# Main.net
KiCad netlist of a schematic drawn in Altium Designer
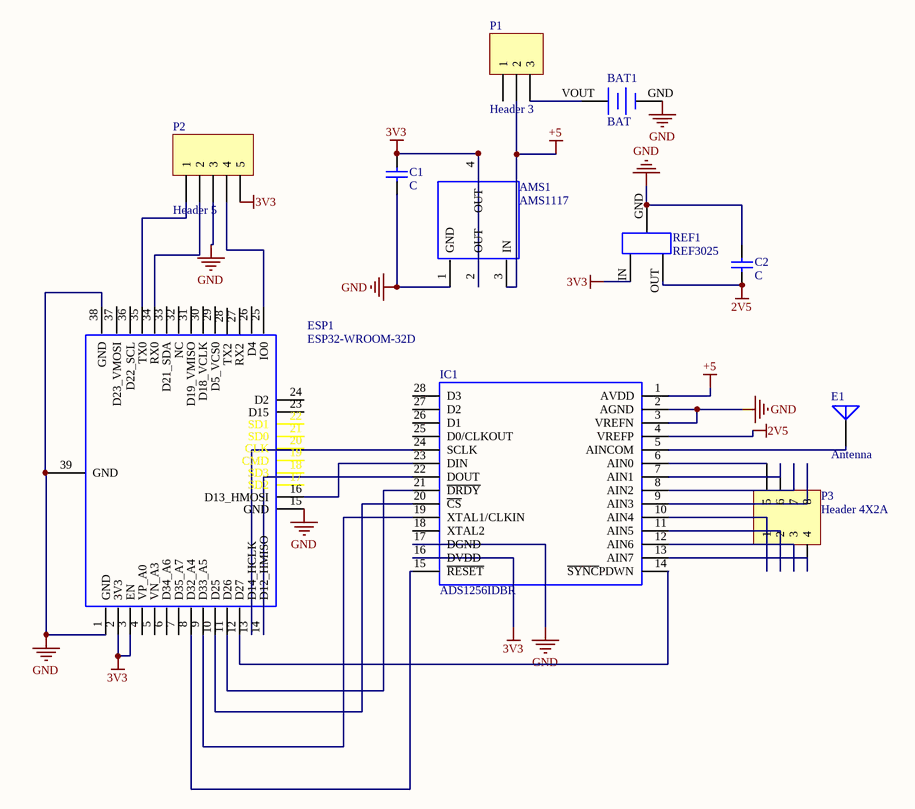
[diagram p0: Main.SchDoc]

(export (version "E")
  (design (tool "Eeschema 10.0.6"))
  (components
    (comp (ref "AMS1")
      (value "AMS1117")
      (footprint "AMS1117")
      (fields (field (name "PUBLISHER") "Altium Limited"))
      (libsource (lib "AlwaysBlue") (part "AMS1117"))
    )
    (comp (ref "BAT1")
      (value "BAT")
      (footprint "CHARGER")
      (fields (field (name "PUBLISHER") "Altium Limited"))
      (libsource (lib "AlwaysBlue") (part "BAT"))
    )
    (comp (ref "C1")
      (value "C")
      (footprint "C0805")
      (fields (field (name "PUBLISHER") "Altium Limited"))
      (libsource (lib "AlwaysBlue") (part "C"))
    )
    (comp (ref "C2")
      (value "C")
      (footprint "C0805")
      (fields (field (name "PUBLISHER") "Altium Limited"))
      (libsource (lib "AlwaysBlue") (part "C"))
    )
    (comp (ref "E1")
      (value "Antenna")
      (footprint "1P")
      (description "Generic Antenna")
      (fields (field (name "PUBLISHER") "Altium Limited"))
      (libsource (lib "Miscellaneous Devices") (part "Antenna"))
    )
    (comp (ref "ESP1")
      (value "ESP32-WROOM-32D")
      (footprint "ESP32WROOM32D")
      (fields (field (name "PUBLISHER") "Altium Limited"))
      (libsource (lib "AlwaysBlue") (part "ESP32-WROOM-32D"))
    )
    (comp (ref "IC1")
      (value "ADS1256IDBR")
      (footprint "ADS1256IDBR")
      (description "Integrated Circuit")
      (fields (field (name "MOUSER PART NUMBER") "595-ADS1256IDBR"))
      (libsource (lib "AlwaysBlue") (part "ADS1256IDBR"))
    )
    (comp (ref "P1")
      (value "Header 3")
      (footprint "3P_SWITCH")
      (description "Header, 3-Pin")
      (fields (field (name "PUBLISHER") "Altium Limited"))
      (libsource (lib "Miscellaneous Connectors") (part "Header 3"))
    )
    (comp (ref "P2")
      (value "Header 5")
      (footprint "5P")
      (description "Header, 5-Pin")
      (fields (field (name "PUBLISHER") "Altium Limited"))
      (libsource (lib "Miscellaneous Connectors") (part "Header 5"))
    )
    (comp (ref "P3")
      (value "Header 4X2A")
      (footprint "ELECTRODE")
      (description "Header, 4-Pin, Dual row")
      (fields (field (name "PUBLISHER") "Altium Limited"))
      (libsource (lib "Miscellaneous Connectors") (part "Header 4X2A"))
    )
    (comp (ref "REF1")
      (value "REF3025")
      (footprint "REF3025_SOT23")
      (libsource (lib "AlwaysBlue") (part "REF3025"))
    )
  )
  (nets
    (net (code "1") (name "+5") (class "Default")
      (node (ref "AMS1") (pin "3") (pinfunction "IN_3") (pintype "power_in"))
      (node (ref "IC1") (pin "1") (pinfunction "AVDD_1") (pintype "passive"))
      (node (ref "P1") (pin "2") (pinfunction "2_2") (pintype "passive"))
    )
    (net (code "2") (name "2V5") (class "Default")
      (node (ref "C2") (pin "1") (pinfunction "1_1") (pintype "passive"))
      (node (ref "IC1") (pin "4") (pinfunction "VREFP_4") (pintype "passive"))
      (node (ref "REF1") (pin "OUT") (pintype "passive"))
    )
    (net (code "3") (name "3V3") (class "Default")
      (node (ref "AMS1") (pin "2") (pinfunction "OUT_2") (pintype "power_in"))
      (node (ref "AMS1") (pin "4") (pinfunction "OUT_4") (pintype "power_in"))
      (node (ref "C1") (pin "2") (pinfunction "2_2") (pintype "passive"))
      (node (ref "ESP1") (pin "2") (pinfunction "3V3_2") (pintype "passive"))
      (node (ref "ESP1") (pin "3") (pinfunction "EN_3") (pintype "passive"))
      (node (ref "IC1") (pin "16") (pinfunction "DVDD_16") (pintype "passive"))
      (node (ref "P2") (pin "5") (pinfunction "5_5") (pintype "passive"))
      (node (ref "REF1") (pin "IN") (pintype "passive"))
    )
    (net (code "4") (name "GND") (class "Default")
      (node (ref "AMS1") (pin "1") (pinfunction "GND_1") (pintype "power_in"))
      (node (ref "BAT1") (pin "GND") (pintype "passive"))
      (node (ref "C1") (pin "1") (pinfunction "1_1") (pintype "passive"))
      (node (ref "C2") (pin "2") (pinfunction "2_2") (pintype "passive"))
      (node (ref "ESP1") (pin "1") (pinfunction "GND_1") (pintype "passive"))
      (node (ref "ESP1") (pin "15") (pinfunction "GND_15") (pintype "passive"))
      (node (ref "ESP1") (pin "38") (pinfunction "GND_38") (pintype "passive"))
      (node (ref "ESP1") (pin "39") (pinfunction "GND_39") (pintype "passive"))
      (node (ref "IC1") (pin "17") (pinfunction "DGND_17") (pintype "passive"))
      (node (ref "IC1") (pin "2") (pinfunction "AGND_2") (pintype "passive"))
      (node (ref "IC1") (pin "3") (pinfunction "VREFN_3") (pintype "passive"))
      (node (ref "P2") (pin "3") (pinfunction "3_3") (pintype "passive"))
      (node (ref "REF1") (pin "GND") (pintype "passive"))
    )
    (net (code "5") (name "Net-(BAT1-PadVOUT)") (class "Default")
      (node (ref "BAT1") (pin "VOUT") (pintype "passive"))
      (node (ref "P1") (pin "3") (pinfunction "3_3") (pintype "passive"))
    )
    (net (code "6") (name "Net-(E1-A)") (class "Default")
      (node (ref "E1") (pin "1") (pinfunction "A_1") (pintype "passive"))
      (node (ref "IC1") (pin "5") (pinfunction "AINCOM_5") (pintype "passive"))
    )
    (net (code "7") (name "Net-(ESP1-D12_HMISO)") (class "Default")
      (node (ref "ESP1") (pin "14") (pinfunction "D12_HMISO_14") (pintype "passive"))
      (node (ref "IC1") (pin "22") (pinfunction "DOUT_22") (pintype "passive"))
    )
    (net (code "8") (name "Net-(ESP1-D13_HMOSI)") (class "Default")
      (node (ref "ESP1") (pin "16") (pinfunction "D13_HMOSI_16") (pintype "passive"))
      (node (ref "IC1") (pin "23") (pinfunction "DIN_23") (pintype "passive"))
    )
    (net (code "9") (name "Net-(ESP1-D14_HCLK)") (class "Default")
      (node (ref "ESP1") (pin "13") (pinfunction "D14_HCLK_13") (pintype "passive"))
      (node (ref "IC1") (pin "24") (pinfunction "SCLK_24") (pintype "passive"))
    )
    (net (code "10") (name "Net-(ESP1-D25)") (class "Default")
      (node (ref "ESP1") (pin "10") (pinfunction "D25_10") (pintype "passive"))
      (node (ref "IC1") (pin "20") (pinfunction "~{CS}_20") (pintype "passive"))
    )
    (net (code "11") (name "Net-(ESP1-D26)") (class "Default")
      (node (ref "ESP1") (pin "11") (pinfunction "D26_11") (pintype "passive"))
      (node (ref "IC1") (pin "21") (pinfunction "~{DRDY}_21") (pintype "passive"))
    )
    (net (code "12") (name "Net-(ESP1-D27)") (class "Default")
      (node (ref "ESP1") (pin "12") (pinfunction "D27_12") (pintype "passive"))
      (node (ref "IC1") (pin "14") (pinfunction "~{SYNC}PDWN_14") (pintype "passive"))
    )
    (net (code "13") (name "Net-(ESP1-D32_A4)") (class "Default")
      (node (ref "ESP1") (pin "8") (pinfunction "D32_A4_8") (pintype "passive"))
      (node (ref "IC1") (pin "15") (pinfunction "~{RESET}_15") (pintype "passive"))
    )
    (net (code "14") (name "Net-(ESP1-D33_A5)") (class "Default")
      (node (ref "ESP1") (pin "9") (pinfunction "D33_A5_9") (pintype "passive"))
      (node (ref "IC1") (pin "19") (pinfunction "XTAL1/CLKIN_19") (pintype "passive"))
    )
    (net (code "15") (name "Net-(ESP1-IO0)") (class "Default")
      (node (ref "ESP1") (pin "25") (pinfunction "IO0_25") (pintype "passive"))
      (node (ref "P2") (pin "4") (pinfunction "4_4") (pintype "passive"))
    )
    (net (code "16") (name "Net-(ESP1-RX0)") (class "Default")
      (node (ref "ESP1") (pin "34") (pinfunction "RX0_34") (pintype "passive"))
      (node (ref "P2") (pin "2") (pinfunction "2_2") (pintype "passive"))
    )
    (net (code "17") (name "Net-(ESP1-TX0)") (class "Default")
      (node (ref "ESP1") (pin "35") (pinfunction "TX0_35") (pintype "passive"))
      (node (ref "P2") (pin "1") (pinfunction "1_1") (pintype "passive"))
    )
    (net (code "18") (name "Net-(IC1-AIN0)") (class "Default")
      (node (ref "IC1") (pin "6") (pinfunction "AIN0_6") (pintype "passive"))
      (node (ref "P3") (pin "5") (pinfunction "5_5") (pintype "passive"))
    )
    (net (code "19") (name "Net-(IC1-AIN1)") (class "Default")
      (node (ref "IC1") (pin "7") (pinfunction "AIN1_7") (pintype "passive"))
      (node (ref "P3") (pin "6") (pinfunction "6_6") (pintype "passive"))
    )
    (net (code "20") (name "Net-(IC1-AIN2)") (class "Default")
      (node (ref "IC1") (pin "8") (pinfunction "AIN2_8") (pintype "passive"))
      (node (ref "P3") (pin "7") (pinfunction "7_7") (pintype "passive"))
    )
    (net (code "21") (name "Net-(IC1-AIN3)") (class "Default")
      (node (ref "IC1") (pin "9") (pinfunction "AIN3_9") (pintype "passive"))
      (node (ref "P3") (pin "8") (pinfunction "8_8") (pintype "passive"))
    )
    (net (code "22") (name "Net-(IC1-AIN4)") (class "Default")
      (node (ref "IC1") (pin "10") (pinfunction "AIN4_10") (pintype "passive"))
      (node (ref "P3") (pin "1") (pinfunction "1_1") (pintype "passive"))
    )
    (net (code "23") (name "Net-(IC1-AIN5)") (class "Default")
      (node (ref "IC1") (pin "11") (pinfunction "AIN5_11") (pintype "passive"))
      (node (ref "P3") (pin "2") (pinfunction "2_2") (pintype "passive"))
    )
    (net (code "24") (name "Net-(IC1-AIN6)") (class "Default")
      (node (ref "IC1") (pin "12") (pinfunction "AIN6_12") (pintype "passive"))
      (node (ref "P3") (pin "3") (pinfunction "3_3") (pintype "passive"))
    )
    (net (code "25") (name "Net-(IC1-AIN7)") (class "Default")
      (node (ref "IC1") (pin "13") (pinfunction "AIN7_13") (pintype "passive"))
      (node (ref "P3") (pin "4") (pinfunction "4_4") (pintype "passive"))
    )
    (net (code "26") (name "unconnected-(ESP1-CLK-Pad20)") (class "Default")
      (node (ref "ESP1") (pin "20") (pinfunction "CLK_20") (pintype "passive"))
    )
    (net (code "27") (name "unconnected-(ESP1-CMD-Pad19)") (class "Default")
      (node (ref "ESP1") (pin "19") (pinfunction "CMD_19") (pintype "passive"))
    )
    (net (code "28") (name "unconnected-(ESP1-D2-Pad24)") (class "Default")
      (node (ref "ESP1") (pin "24") (pinfunction "D2_24") (pintype "passive"))
    )
    (net (code "29") (name "unconnected-(ESP1-D4-Pad26)") (class "Default")
      (node (ref "ESP1") (pin "26") (pinfunction "D4_26") (pintype "passive"))
    )
    (net (code "30") (name "unconnected-(ESP1-D5_VCS0-Pad29)") (class "Default")
      (node (ref "ESP1") (pin "29") (pinfunction "D5_VCS0_29") (pintype "passive"))
    )
    (net (code "31") (name "unconnected-(ESP1-D15-Pad23)") (class "Default")
      (node (ref "ESP1") (pin "23") (pinfunction "D15_23") (pintype "passive"))
    )
    (net (code "32") (name "unconnected-(ESP1-D18_VCLK-Pad30)") (class "Default")
      (node (ref "ESP1") (pin "30") (pinfunction "D18_VCLK_30") (pintype "passive"))
    )
    (net (code "33") (name "unconnected-(ESP1-D19_VMISO-Pad31)") (class "Default")
      (node (ref "ESP1") (pin "31") (pinfunction "D19_VMISO_31") (pintype "passive"))
    )
    (net (code "34") (name "unconnected-(ESP1-D21_SDA-Pad33)") (class "Default")
      (node (ref "ESP1") (pin "33") (pinfunction "D21_SDA_33") (pintype "passive"))
    )
    (net (code "35") (name "unconnected-(ESP1-D22_SCL-Pad36)") (class "Default")
      (node (ref "ESP1") (pin "36") (pinfunction "D22_SCL_36") (pintype "passive"))
    )
    (net (code "36") (name "unconnected-(ESP1-D23_VMOSI-Pad37)") (class "Default")
      (node (ref "ESP1") (pin "37") (pinfunction "D23_VMOSI_37") (pintype "passive"))
    )
    (net (code "37") (name "unconnected-(ESP1-D34_A6-Pad6)") (class "Default")
      (node (ref "ESP1") (pin "6") (pinfunction "D34_A6_6") (pintype "passive"))
    )
    (net (code "38") (name "unconnected-(ESP1-D35_A7-Pad7)") (class "Default")
      (node (ref "ESP1") (pin "7") (pinfunction "D35_A7_7") (pintype "passive"))
    )
    (net (code "39") (name "unconnected-(ESP1-NC-Pad32)") (class "Default")
      (node (ref "ESP1") (pin "32") (pinfunction "NC_32") (pintype "passive"))
    )
    (net (code "40") (name "unconnected-(ESP1-RX2-Pad27)") (class "Default")
      (node (ref "ESP1") (pin "27") (pinfunction "RX2_27") (pintype "passive"))
    )
    (net (code "41") (name "unconnected-(ESP1-SD0-Pad21)") (class "Default")
      (node (ref "ESP1") (pin "21") (pinfunction "SD0_21") (pintype "passive"))
    )
    (net (code "42") (name "unconnected-(ESP1-SD1-Pad22)") (class "Default")
      (node (ref "ESP1") (pin "22") (pinfunction "SD1_22") (pintype "passive"))
    )
    (net (code "43") (name "unconnected-(ESP1-SD2-Pad17)") (class "Default")
      (node (ref "ESP1") (pin "17") (pinfunction "SD2_17") (pintype "passive"))
    )
    (net (code "44") (name "unconnected-(ESP1-SD3-Pad18)") (class "Default")
      (node (ref "ESP1") (pin "18") (pinfunction "SD3_18") (pintype "passive"))
    )
    (net (code "45") (name "unconnected-(ESP1-TX2-Pad28)") (class "Default")
      (node (ref "ESP1") (pin "28") (pinfunction "TX2_28") (pintype "passive"))
    )
    (net (code "46") (name "unconnected-(ESP1-VN_A3-Pad5)") (class "Default")
      (node (ref "ESP1") (pin "5") (pinfunction "VN_A3_5") (pintype "passive"))
    )
    (net (code "47") (name "unconnected-(ESP1-VP_A0-Pad4)") (class "Default")
      (node (ref "ESP1") (pin "4") (pinfunction "VP_A0_4") (pintype "passive"))
    )
    (net (code "48") (name "unconnected-(IC1-D0{slash}CLKOUT-Pad25)") (class "Default")
      (node (ref "IC1") (pin "25") (pinfunction "D0/CLKOUT_25") (pintype "passive"))
    )
    (net (code "49") (name "unconnected-(IC1-D1-Pad26)") (class "Default")
      (node (ref "IC1") (pin "26") (pinfunction "D1_26") (pintype "passive"))
    )
    (net (code "50") (name "unconnected-(IC1-D2-Pad27)") (class "Default")
      (node (ref "IC1") (pin "27") (pinfunction "D2_27") (pintype "passive"))
    )
    (net (code "51") (name "unconnected-(IC1-D3-Pad28)") (class "Default")
      (node (ref "IC1") (pin "28") (pinfunction "D3_28") (pintype "passive"))
    )
    (net (code "52") (name "unconnected-(IC1-XTAL2-Pad18)") (class "Default")
      (node (ref "IC1") (pin "18") (pinfunction "XTAL2_18") (pintype "passive"))
    )
    (net (code "53") (name "unconnected-(P1-Pad1)") (class "Default")
      (node (ref "P1") (pin "1") (pinfunction "1_1") (pintype "passive"))
    )
  )
)
